# Chime_PCB_v2_7_9_18.net
KiCad netlist of a schematic drawn in EAGLE
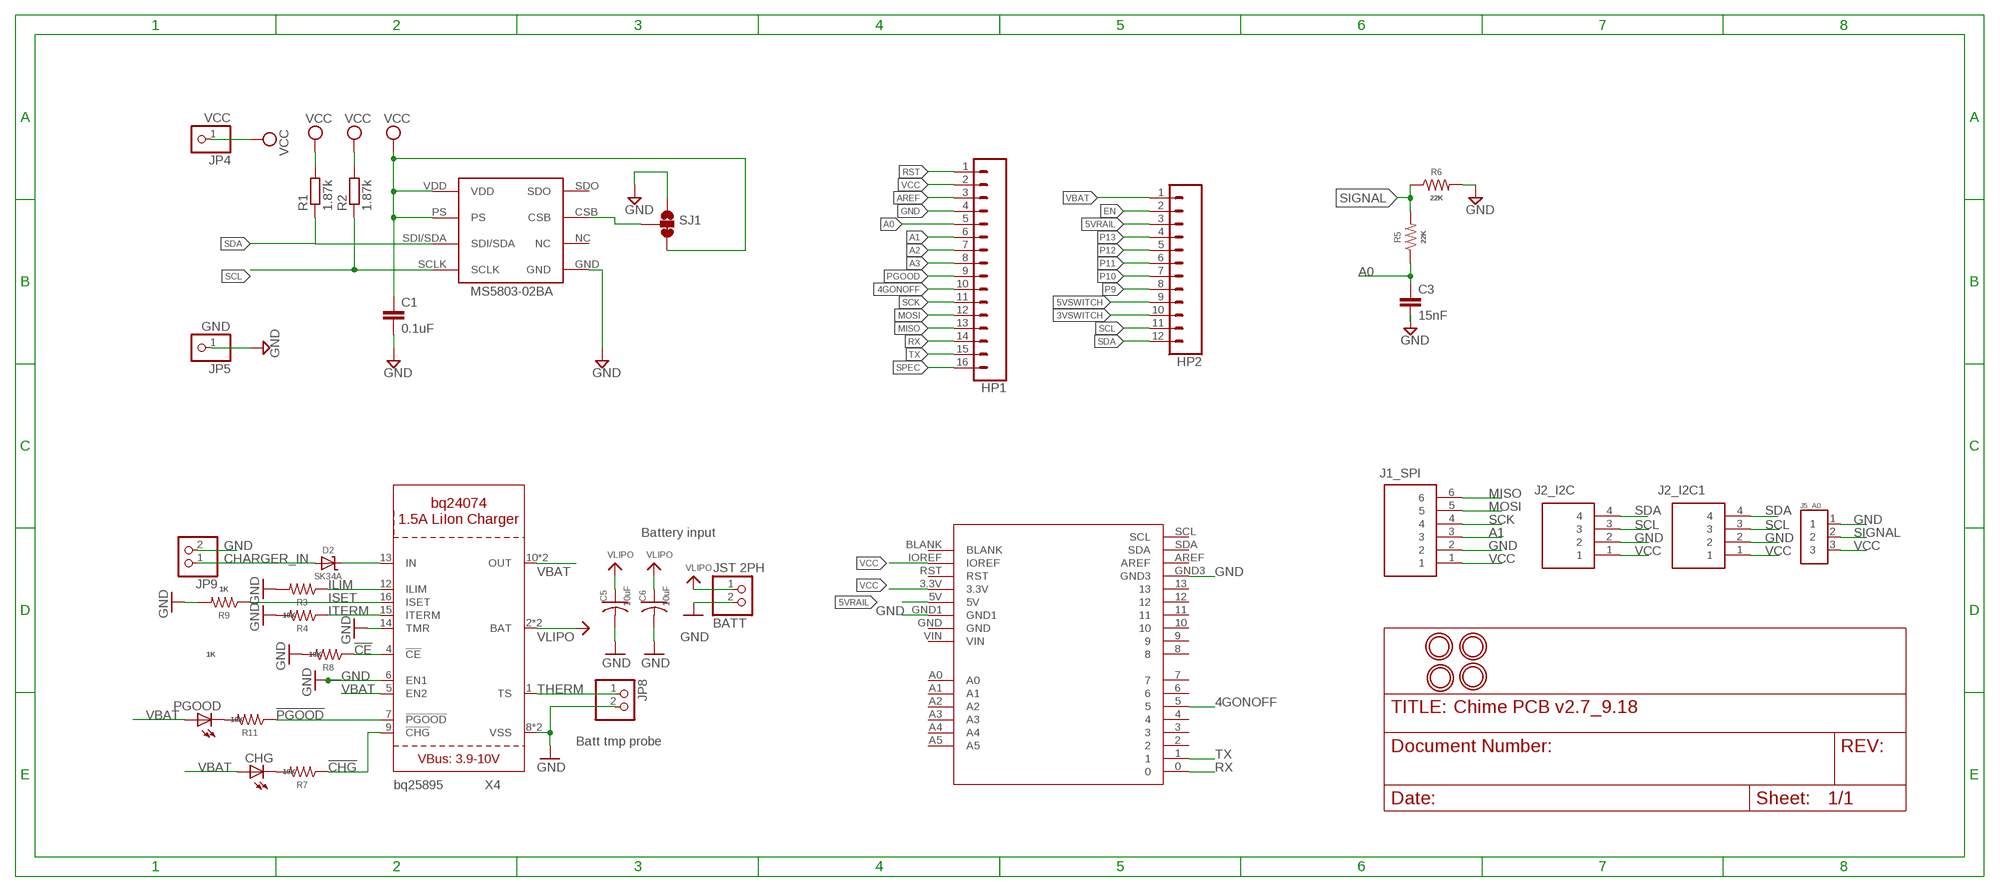
[diagram p0: schematic, sheet 1]

(export (version "E")
  (design (tool "Eeschema 10.0.6"))
  (components
    (comp (ref "BATT")
      (value "JST 2PH")
      (footprint "eagle-import:JST-PH-2-SMT-RA")
      (libsource (lib "eagle-import") (part "JST_2PIN-SMT-RA"))
    )
    (comp (ref "C1")
      (value "0.1uF")
      (footprint "eagle-import:C0805")
      (libsource (lib "eagle-import") (part "C-EUC0805"))
    )
    (comp (ref "C3")
      (value "15nF")
      (footprint "eagle-import:C0805")
      (libsource (lib "eagle-import") (part "C-EUC0805"))
    )
    (comp (ref "C5")
      (value "10uF")
      (footprint "eagle-import:C0805K")
      (libsource (lib "eagle-import") (part "C-USC0805K"))
    )
    (comp (ref "C6")
      (value "10uF")
      (footprint "eagle-import:C0805K")
      (libsource (lib "eagle-import") (part "C-USC0805K"))
    )
    (comp (ref "CHG")
      (value "LEDCHIPLED_0805")
      (footprint "eagle-import:CHIPLED_0805")
      (libsource (lib "eagle-import") (part "LEDCHIPLED_0805"))
    )
    (comp (ref "D2")
      (value "SK34A")
      (footprint "eagle-import:SMADIODE")
      (libsource (lib "eagle-import") (part "DIODE-SCHOTTKYSMA"))
    )
    (comp (ref "HP1")
      (value "CONN_16")
      (footprint "eagle-import:1X16")
      (libsource (lib "eagle-import") (part "CONN_16"))
    )
    (comp (ref "HP2")
      (value "CONN_12")
      (footprint "eagle-import:1X12")
      (libsource (lib "eagle-import") (part "CONN_12"))
    )
    (comp (ref "J1_SPI")
      (value "1725698")
      (footprint "eagle-import:1725698")
      (fields (field (name "MOUSER_PART_NUMBER") "651-1725698"))
      (libsource (lib "eagle-import") (part "1725698"))
    )
    (comp (ref "J2_I2C")
      (value "1725672")
      (footprint "eagle-import:1725672")
      (fields (field (name "MOUSER_PART_NUMBER") "651-1725672"))
      (libsource (lib "eagle-import") (part "1725672"))
    )
    (comp (ref "J2_I2C1")
      (value "1725672")
      (footprint "eagle-import:1725672")
      (fields (field (name "MOUSER_PART_NUMBER") "651-1725672"))
      (libsource (lib "eagle-import") (part "1725672"))
    )
    (comp (ref "J5_A0")
      (value "282834-3")
      (footprint "eagle-import:TE_282834-3")
      (fields (field (name "MF") "TE Connectivity"))
      (libsource (lib "eagle-import") (part "282834-3"))
    )
    (comp (ref "JP4")
      (value "VCC")
      (footprint "eagle-import:1X01")
      (libsource (lib "eagle-import") (part "PINHD-1X1"))
    )
    (comp (ref "JP5")
      (value "GND")
      (footprint "eagle-import:1X01")
      (libsource (lib "eagle-import") (part "PINHD-1X1"))
    )
    (comp (ref "JP8")
      (value "PINHD-1X2")
      (footprint "eagle-import:1X02")
      (libsource (lib "eagle-import") (part "PINHD-1X2"))
    )
    (comp (ref "JP9")
      (value "PINHD-1X2")
      (footprint "eagle-import:1X02")
      (libsource (lib "eagle-import") (part "PINHD-1X2"))
    )
    (comp (ref "PGOOD")
      (value "PGOOD")
      (footprint "eagle-import:CHIPLED_0805")
      (libsource (lib "eagle-import") (part "LEDCHIPLED_0805"))
    )
    (comp (ref "R1")
      (value "1.87k")
      (footprint "eagle-import:R0805")
      (libsource (lib "eagle-import") (part "R-EU_R0805"))
    )
    (comp (ref "R2")
      (value "1.87k")
      (footprint "eagle-import:R0805")
      (libsource (lib "eagle-import") (part "R-EU_R0805"))
    )
    (comp (ref "R3")
      (value "1K")
      (footprint "eagle-import:M0805")
      (libsource (lib "eagle-import") (part "R-US_M0805"))
    )
    (comp (ref "R4")
      (value "10K")
      (footprint "eagle-import:M0805")
      (libsource (lib "eagle-import") (part "R-US_M0805"))
    )
    (comp (ref "R5")
      (value "22K")
      (footprint "eagle-import:M0805")
      (libsource (lib "eagle-import") (part "R-US_M0805"))
    )
    (comp (ref "R6")
      (value "22K")
      (footprint "eagle-import:M0805")
      (libsource (lib "eagle-import") (part "R-US_M0805"))
    )
    (comp (ref "R7")
      (value "10K")
      (footprint "eagle-import:M0805")
      (libsource (lib "eagle-import") (part "R-US_M0805"))
    )
    (comp (ref "R8")
      (value "10K")
      (footprint "eagle-import:M0805")
      (libsource (lib "eagle-import") (part "R-US_M0805"))
    )
    (comp (ref "R9")
      (value "1K")
      (footprint "eagle-import:M0805")
      (libsource (lib "eagle-import") (part "R-US_M0805"))
    )
    (comp (ref "R11")
      (value "10K")
      (footprint "eagle-import:M0805")
      (libsource (lib "eagle-import") (part "R-US_M0805"))
    )
    (comp (ref "SJ1")
      (value "JUMPER-SMT_3_1-NC_TRACE_SILK")
      (footprint "eagle-import:SMT-JUMPER_3_1-NC_TRACE_SILK")
      (libsource (lib "eagle-import") (part "JUMPER-SMT_3_1-NC_TRACE_SILK"))
    )
    (comp (ref "U$1")
      (value "LTE_BOARD")
      (footprint "eagle-import:LTE_BOARD_FOOTPRINT")
      (libsource (lib "eagle-import") (part "LTE_BOARD"))
    )
    (comp (ref "U$2")
      (value "MOUNTINGHOLE2.5")
      (footprint "eagle-import:MOUNTINGHOLE_2.5_PLATED")
      (libsource (lib "eagle-import") (part "MOUNTINGHOLE2.5"))
    )
    (comp (ref "U$3")
      (value "MOUNTINGHOLE2.5")
      (footprint "eagle-import:MOUNTINGHOLE_2.5_PLATED")
      (libsource (lib "eagle-import") (part "MOUNTINGHOLE2.5"))
    )
    (comp (ref "U$4")
      (value "MOUNTINGHOLE2.5")
      (footprint "eagle-import:MOUNTINGHOLE_2.5_PLATED")
      (libsource (lib "eagle-import") (part "MOUNTINGHOLE2.5"))
    )
    (comp (ref "U$5")
      (value "MOUNTINGHOLE2.5")
      (footprint "eagle-import:MOUNTINGHOLE_2.5_PLATED")
      (libsource (lib "eagle-import") (part "MOUNTINGHOLE2.5"))
    )
    (comp (ref "U1")
      (value "MS5803-02BA")
      (footprint "eagle-import:MS5803-02BA")
      (libsource (lib "eagle-import") (part "MS5803-02BA"))
    )
    (comp (ref "X4")
      (value "BQ24074")
      (footprint "eagle-import:QFN16_3MM")
      (libsource (lib "eagle-import") (part "BQ24074"))
    )
  )
  (nets
    (net (code "1") (name "/CHARGER_IN") (class "Default")
      (node (ref "D2") (pin "A") (pinfunction "A_A") (pintype "passive"))
      (node (ref "JP9") (pin "1") (pinfunction "1_1") (pintype "passive"))
    )
    (net (code "2") (name "/ILIM") (class "Default")
      (node (ref "R3") (pin "1") (pinfunction "1_1") (pintype "passive"))
      (node (ref "X4") (pin "12") (pinfunction "ILIM_12") (pintype "input"))
    )
    (net (code "3") (name "/ISET") (class "Default")
      (node (ref "R9") (pin "1") (pinfunction "1_1") (pintype "passive"))
      (node (ref "X4") (pin "16") (pinfunction "ISET_16") (pintype "input"))
    )
    (net (code "4") (name "/ITERM") (class "Default")
      (node (ref "R4") (pin "1") (pinfunction "1_1") (pintype "passive"))
      (node (ref "X4") (pin "15") (pinfunction "ITERM_15") (pintype "input"))
    )
    (net (code "5") (name "/THERM") (class "Default")
      (node (ref "JP8") (pin "1") (pinfunction "1_1") (pintype "passive"))
      (node (ref "X4") (pin "1") (pinfunction "TS_1") (pintype "input"))
    )
    (net (code "6") (name "/~{CE}") (class "Default")
      (node (ref "R8") (pin "1") (pinfunction "1_1") (pintype "passive"))
      (node (ref "X4") (pin "4") (pinfunction "~{CE}_4") (pintype "input"))
    )
    (net (code "7") (name "/~{CHG}") (class "Default")
      (node (ref "R7") (pin "1") (pinfunction "1_1") (pintype "passive"))
      (node (ref "X4") (pin "9") (pinfunction "~{CHG}_9") (pintype "output"))
    )
    (net (code "8") (name "/~{PGOOD}") (class "Default")
      (node (ref "R11") (pin "1") (pinfunction "1_1") (pintype "passive"))
      (node (ref "X4") (pin "7") (pinfunction "~{PGOOD}_7") (pintype "output"))
    )
    (net (code "9") (name "3VSWITCH") (class "Default")
      (node (ref "HP2") (pin "10") (pinfunction "10_10") (pintype "passive"))
    )
    (net (code "10") (name "4GONOFF") (class "Default")
      (node (ref "HP1") (pin "10") (pinfunction "10_10") (pintype "passive"))
      (node (ref "U$1") (pin "5") (pinfunction "5_5") (pintype "bidirectional"))
    )
    (net (code "11") (name "5VRAIL") (class "Default")
      (node (ref "HP2") (pin "3") (pinfunction "3_3") (pintype "passive"))
      (node (ref "U$1") (pin "5V") (pinfunction "5V_5V") (pintype "bidirectional"))
    )
    (net (code "12") (name "5VSWITCH") (class "Default")
      (node (ref "HP2") (pin "9") (pinfunction "9_9") (pintype "passive"))
    )
    (net (code "13") (name "A0") (class "Default")
      (node (ref "C3") (pin "1") (pinfunction "1_1") (pintype "passive"))
      (node (ref "HP1") (pin "5") (pinfunction "5_5") (pintype "passive"))
      (node (ref "R5") (pin "1") (pinfunction "1_1") (pintype "passive"))
    )
    (net (code "14") (name "A1") (class "Default")
      (node (ref "HP1") (pin "6") (pinfunction "6_6") (pintype "passive"))
      (node (ref "J1_SPI") (pin "3") (pinfunction "3_3") (pintype "bidirectional"))
    )
    (net (code "15") (name "A2") (class "Default")
      (node (ref "HP1") (pin "7") (pinfunction "7_7") (pintype "passive"))
    )
    (net (code "16") (name "A3") (class "Default")
      (node (ref "HP1") (pin "8") (pinfunction "8_8") (pintype "passive"))
    )
    (net (code "17") (name "AREF") (class "Default")
      (node (ref "HP1") (pin "3") (pinfunction "3_3") (pintype "passive"))
    )
    (net (code "18") (name "EN") (class "Default")
      (node (ref "HP2") (pin "2") (pinfunction "2_2") (pintype "passive"))
    )
    (net (code "19") (name "GND") (class "Default")
      (node (ref "BATT") (pin "2") (pinfunction "1_2") (pintype "passive"))
      (node (ref "C1") (pin "2") (pinfunction "2_2") (pintype "passive"))
      (node (ref "C3") (pin "2") (pinfunction "2_2") (pintype "passive"))
      (node (ref "C5") (pin "2") (pinfunction "2_2") (pintype "passive"))
      (node (ref "C6") (pin "2") (pinfunction "2_2") (pintype "passive"))
      (node (ref "HP1") (pin "4") (pinfunction "4_4") (pintype "passive"))
      (node (ref "J1_SPI") (pin "2") (pinfunction "2_2") (pintype "bidirectional"))
      (node (ref "J2_I2C") (pin "2") (pinfunction "2_2") (pintype "bidirectional"))
      (node (ref "J2_I2C1") (pin "2") (pinfunction "2_2") (pintype "bidirectional"))
      (node (ref "J5_A0") (pin "1") (pinfunction "1_1") (pintype "passive"))
      (node (ref "JP5") (pin "1") (pinfunction "1_1") (pintype "passive"))
      (node (ref "JP8") (pin "2") (pinfunction "2_2") (pintype "passive"))
      (node (ref "JP9") (pin "2") (pinfunction "2_2") (pintype "passive"))
      (node (ref "R3") (pin "2") (pinfunction "2_2") (pintype "passive"))
      (node (ref "R4") (pin "2") (pinfunction "2_2") (pintype "passive"))
      (node (ref "R6") (pin "2") (pinfunction "2_2") (pintype "passive"))
      (node (ref "R8") (pin "2") (pinfunction "2_2") (pintype "passive"))
      (node (ref "R9") (pin "2") (pinfunction "2_2") (pintype "passive"))
      (node (ref "SJ1") (pin "1") (pinfunction "1_1") (pintype "passive"))
      (node (ref "U$1") (pin "GND1") (pinfunction "GND1_GND1") (pintype "bidirectional"))
      (node (ref "U$1") (pin "GND3") (pinfunction "GND3_GND3") (pintype "bidirectional"))
      (node (ref "U1") (pin "GND") (pinfunction "GND_GND") (pintype "bidirectional"))
      (node (ref "X4") (pin "14") (pinfunction "TMR_14") (pintype "input"))
      (node (ref "X4") (pin "6") (pinfunction "EN1_6") (pintype "input"))
      (node (ref "X4") (pin "8") (pinfunction "VSS_8") (pintype "power_in"))
      (node (ref "X4") (pin "THERMAL") (pinfunction "VSS_THERMAL") (pintype "power_in"))
    )
    (net (code "20") (name "MISO") (class "Default")
      (node (ref "HP1") (pin "13") (pinfunction "13_13") (pintype "passive"))
      (node (ref "J1_SPI") (pin "6") (pinfunction "6_6") (pintype "bidirectional"))
    )
    (net (code "21") (name "MOSI") (class "Default")
      (node (ref "HP1") (pin "12") (pinfunction "12_12") (pintype "passive"))
      (node (ref "J1_SPI") (pin "5") (pinfunction "5_5") (pintype "bidirectional"))
    )
    (net (code "22") (name "Net-(CHG-PadC)") (class "Default")
      (node (ref "CHG") (pin "C") (pinfunction "C_C") (pintype "passive"))
      (node (ref "R7") (pin "2") (pinfunction "2_2") (pintype "passive"))
    )
    (net (code "23") (name "Net-(PGOOD-PadC)") (class "Default")
      (node (ref "PGOOD") (pin "C") (pinfunction "C_C") (pintype "passive"))
      (node (ref "R11") (pin "2") (pinfunction "2_2") (pintype "passive"))
    )
    (net (code "24") (name "Net-(SJ1-Pad2)") (class "Default")
      (node (ref "SJ1") (pin "2") (pinfunction "2_2") (pintype "passive"))
      (node (ref "U1") (pin "CSB") (pinfunction "CSB_CSB") (pintype "bidirectional"))
    )
    (net (code "25") (name "Net-(X4-IN)") (class "Default")
      (node (ref "D2") (pin "C") (pinfunction "C_C") (pintype "passive"))
      (node (ref "X4") (pin "13") (pinfunction "IN_13") (pintype "power_in"))
    )
    (net (code "26") (name "P9") (class "Default")
      (node (ref "HP2") (pin "8") (pinfunction "8_8") (pintype "passive"))
    )
    (net (code "27") (name "P10") (class "Default")
      (node (ref "HP2") (pin "7") (pinfunction "7_7") (pintype "passive"))
    )
    (net (code "28") (name "P11") (class "Default")
      (node (ref "HP2") (pin "6") (pinfunction "6_6") (pintype "passive"))
    )
    (net (code "29") (name "P12") (class "Default")
      (node (ref "HP2") (pin "5") (pinfunction "5_5") (pintype "passive"))
    )
    (net (code "30") (name "P13") (class "Default")
      (node (ref "HP2") (pin "4") (pinfunction "4_4") (pintype "passive"))
    )
    (net (code "31") (name "PGOOD") (class "Default")
      (node (ref "HP1") (pin "9") (pinfunction "9_9") (pintype "passive"))
    )
    (net (code "32") (name "RST") (class "Default")
      (node (ref "HP1") (pin "1") (pinfunction "1_1") (pintype "passive"))
    )
    (net (code "33") (name "RX") (class "Default")
      (node (ref "HP1") (pin "14") (pinfunction "14_14") (pintype "passive"))
      (node (ref "U$1") (pin "0") (pinfunction "0_0") (pintype "bidirectional"))
    )
    (net (code "34") (name "SCK") (class "Default")
      (node (ref "HP1") (pin "11") (pinfunction "11_11") (pintype "passive"))
      (node (ref "J1_SPI") (pin "4") (pinfunction "4_4") (pintype "bidirectional"))
    )
    (net (code "35") (name "SCL") (class "Default")
      (node (ref "HP2") (pin "11") (pinfunction "11_11") (pintype "passive"))
      (node (ref "J2_I2C") (pin "3") (pinfunction "3_3") (pintype "bidirectional"))
      (node (ref "J2_I2C1") (pin "3") (pinfunction "3_3") (pintype "bidirectional"))
      (node (ref "R2") (pin "1") (pinfunction "1_1") (pintype "passive"))
      (node (ref "U1") (pin "SCLK") (pinfunction "SCLK_SCLK") (pintype "bidirectional"))
    )
    (net (code "36") (name "SDA") (class "Default")
      (node (ref "HP2") (pin "12") (pinfunction "12_12") (pintype "passive"))
      (node (ref "J2_I2C") (pin "4") (pinfunction "4_4") (pintype "bidirectional"))
      (node (ref "J2_I2C1") (pin "4") (pinfunction "4_4") (pintype "bidirectional"))
      (node (ref "R1") (pin "1") (pinfunction "1_1") (pintype "passive"))
      (node (ref "U1") (pin "SDI/SDA") (pinfunction "SDI/SDA_SDI/SDA") (pintype "bidirectional"))
    )
    (net (code "37") (name "SIGNAL") (class "Default")
      (node (ref "J5_A0") (pin "2") (pinfunction "2_2") (pintype "passive"))
      (node (ref "R5") (pin "2") (pinfunction "2_2") (pintype "passive"))
      (node (ref "R6") (pin "1") (pinfunction "1_1") (pintype "passive"))
    )
    (net (code "38") (name "SPEC") (class "Default")
      (node (ref "HP1") (pin "16") (pinfunction "16_16") (pintype "passive"))
    )
    (net (code "39") (name "TX") (class "Default")
      (node (ref "HP1") (pin "15") (pinfunction "15_15") (pintype "passive"))
      (node (ref "U$1") (pin "1") (pinfunction "1_1") (pintype "bidirectional"))
    )
    (net (code "40") (name "VBAT") (class "Default")
      (node (ref "CHG") (pin "A") (pinfunction "A_A") (pintype "passive"))
      (node (ref "HP2") (pin "1") (pinfunction "1_1") (pintype "passive"))
      (node (ref "PGOOD") (pin "A") (pinfunction "A_A") (pintype "passive"))
      (node (ref "X4") (pin "10") (pinfunction "OUT_10") (pintype "output"))
      (node (ref "X4") (pin "11") (pinfunction "OUT_11") (pintype "output"))
      (node (ref "X4") (pin "5") (pinfunction "EN2_5") (pintype "input"))
    )
    (net (code "41") (name "VCC") (class "Default")
      (node (ref "C1") (pin "1") (pinfunction "1_1") (pintype "passive"))
      (node (ref "HP1") (pin "2") (pinfunction "2_2") (pintype "passive"))
      (node (ref "J1_SPI") (pin "1") (pinfunction "1_1") (pintype "bidirectional"))
      (node (ref "J2_I2C") (pin "1") (pinfunction "1_1") (pintype "bidirectional"))
      (node (ref "J2_I2C1") (pin "1") (pinfunction "1_1") (pintype "bidirectional"))
      (node (ref "J5_A0") (pin "3") (pinfunction "3_3") (pintype "passive"))
      (node (ref "JP4") (pin "1") (pinfunction "1_1") (pintype "passive"))
      (node (ref "R1") (pin "2") (pinfunction "2_2") (pintype "passive"))
      (node (ref "R2") (pin "2") (pinfunction "2_2") (pintype "passive"))
      (node (ref "SJ1") (pin "3") (pinfunction "3_3") (pintype "passive"))
      (node (ref "U$1") (pin "3.3V") (pinfunction "3.3V_3.3V") (pintype "bidirectional"))
      (node (ref "U$1") (pin "IOREF") (pinfunction "IOREF_IOREF") (pintype "bidirectional"))
      (node (ref "U1") (pin "PS") (pinfunction "PS_PS") (pintype "bidirectional"))
      (node (ref "U1") (pin "VDD") (pinfunction "VDD_VDD") (pintype "bidirectional"))
    )
    (net (code "42") (name "VLIPO") (class "Default")
      (node (ref "BATT") (pin "1") (pinfunction "2_1") (pintype "passive"))
      (node (ref "C5") (pin "1") (pinfunction "1_1") (pintype "passive"))
      (node (ref "C6") (pin "1") (pinfunction "1_1") (pintype "passive"))
      (node (ref "X4") (pin "2") (pinfunction "BAT_2") (pintype "input"))
      (node (ref "X4") (pin "3") (pinfunction "BAT_3") (pintype "input"))
    )
    (net (code "43") (name "unconnected-(U$1-Pad2)") (class "Default")
      (node (ref "U$1") (pin "2") (pinfunction "2_2") (pintype "bidirectional"))
    )
    (net (code "44") (name "unconnected-(U$1-Pad3)") (class "Default")
      (node (ref "U$1") (pin "3") (pinfunction "3_3") (pintype "bidirectional"))
    )
    (net (code "45") (name "unconnected-(U$1-Pad4)") (class "Default")
      (node (ref "U$1") (pin "4") (pinfunction "4_4") (pintype "bidirectional"))
    )
    (net (code "46") (name "unconnected-(U$1-Pad6)") (class "Default")
      (node (ref "U$1") (pin "6") (pinfunction "6_6") (pintype "bidirectional"))
    )
    (net (code "47") (name "unconnected-(U$1-Pad7)") (class "Default")
      (node (ref "U$1") (pin "7") (pinfunction "7_7") (pintype "bidirectional"))
    )
    (net (code "48") (name "unconnected-(U$1-Pad8)") (class "Default")
      (node (ref "U$1") (pin "8") (pinfunction "8_8") (pintype "bidirectional"))
    )
    (net (code "49") (name "unconnected-(U$1-Pad9)") (class "Default")
      (node (ref "U$1") (pin "9") (pinfunction "9_9") (pintype "bidirectional"))
    )
    (net (code "50") (name "unconnected-(U$1-Pad10)") (class "Default")
      (node (ref "U$1") (pin "10") (pinfunction "10_10") (pintype "bidirectional"))
    )
    (net (code "51") (name "unconnected-(U$1-Pad11)") (class "Default")
      (node (ref "U$1") (pin "11") (pinfunction "11_11") (pintype "bidirectional"))
    )
    (net (code "52") (name "unconnected-(U$1-Pad12)") (class "Default")
      (node (ref "U$1") (pin "12") (pinfunction "12_12") (pintype "bidirectional"))
    )
    (net (code "53") (name "unconnected-(U$1-Pad13)") (class "Default")
      (node (ref "U$1") (pin "13") (pinfunction "13_13") (pintype "bidirectional"))
    )
    (net (code "54") (name "unconnected-(U$1-PadA0)") (class "Default")
      (node (ref "U$1") (pin "A0") (pinfunction "A0_A0") (pintype "bidirectional"))
    )
    (net (code "55") (name "unconnected-(U$1-PadA1)") (class "Default")
      (node (ref "U$1") (pin "A1") (pinfunction "A1_A1") (pintype "bidirectional"))
    )
    (net (code "56") (name "unconnected-(U$1-PadA2)") (class "Default")
      (node (ref "U$1") (pin "A2") (pinfunction "A2_A2") (pintype "bidirectional"))
    )
    (net (code "57") (name "unconnected-(U$1-PadA3)") (class "Default")
      (node (ref "U$1") (pin "A3") (pinfunction "A3_A3") (pintype "bidirectional"))
    )
    (net (code "58") (name "unconnected-(U$1-PadA4)") (class "Default")
      (node (ref "U$1") (pin "A4") (pinfunction "A4_A4") (pintype "bidirectional"))
    )
    (net (code "59") (name "unconnected-(U$1-PadA5)") (class "Default")
      (node (ref "U$1") (pin "A5") (pinfunction "A5_A5") (pintype "bidirectional"))
    )
    (net (code "60") (name "unconnected-(U$1-PadAREF)") (class "Default")
      (node (ref "U$1") (pin "AREF") (pinfunction "AREF_AREF") (pintype "bidirectional"))
    )
    (net (code "61") (name "unconnected-(U$1-PadBLANK)") (class "Default")
      (node (ref "U$1") (pin "BLANK") (pinfunction "BLANK_BLANK") (pintype "bidirectional"))
    )
    (net (code "62") (name "unconnected-(U$1-PadGND)") (class "Default")
      (node (ref "U$1") (pin "GND") (pinfunction "GND_GND") (pintype "bidirectional"))
    )
    (net (code "63") (name "unconnected-(U$1-PadRST)") (class "Default")
      (node (ref "U$1") (pin "RST") (pinfunction "RST_RST") (pintype "bidirectional"))
    )
    (net (code "64") (name "unconnected-(U$1-PadSCL)") (class "Default")
      (node (ref "U$1") (pin "SCL") (pinfunction "SCL_SCL") (pintype "bidirectional"))
    )
    (net (code "65") (name "unconnected-(U$1-PadSDA)") (class "Default")
      (node (ref "U$1") (pin "SDA") (pinfunction "SDA_SDA") (pintype "bidirectional"))
    )
    (net (code "66") (name "unconnected-(U$1-PadVIN)") (class "Default")
      (node (ref "U$1") (pin "VIN") (pinfunction "VIN_VIN") (pintype "bidirectional"))
    )
    (net (code "67") (name "unconnected-(U1-PadNC)") (class "Default")
      (node (ref "U1") (pin "NC") (pinfunction "NC_NC") (pintype "bidirectional"))
    )
    (net (code "68") (name "unconnected-(U1-PadSDO)") (class "Default")
      (node (ref "U1") (pin "SDO") (pinfunction "SDO_SDO") (pintype "bidirectional"))
    )
  )
)
